# config-bank2.net
KiCad netlist of a schematic drawn in Altium Designer
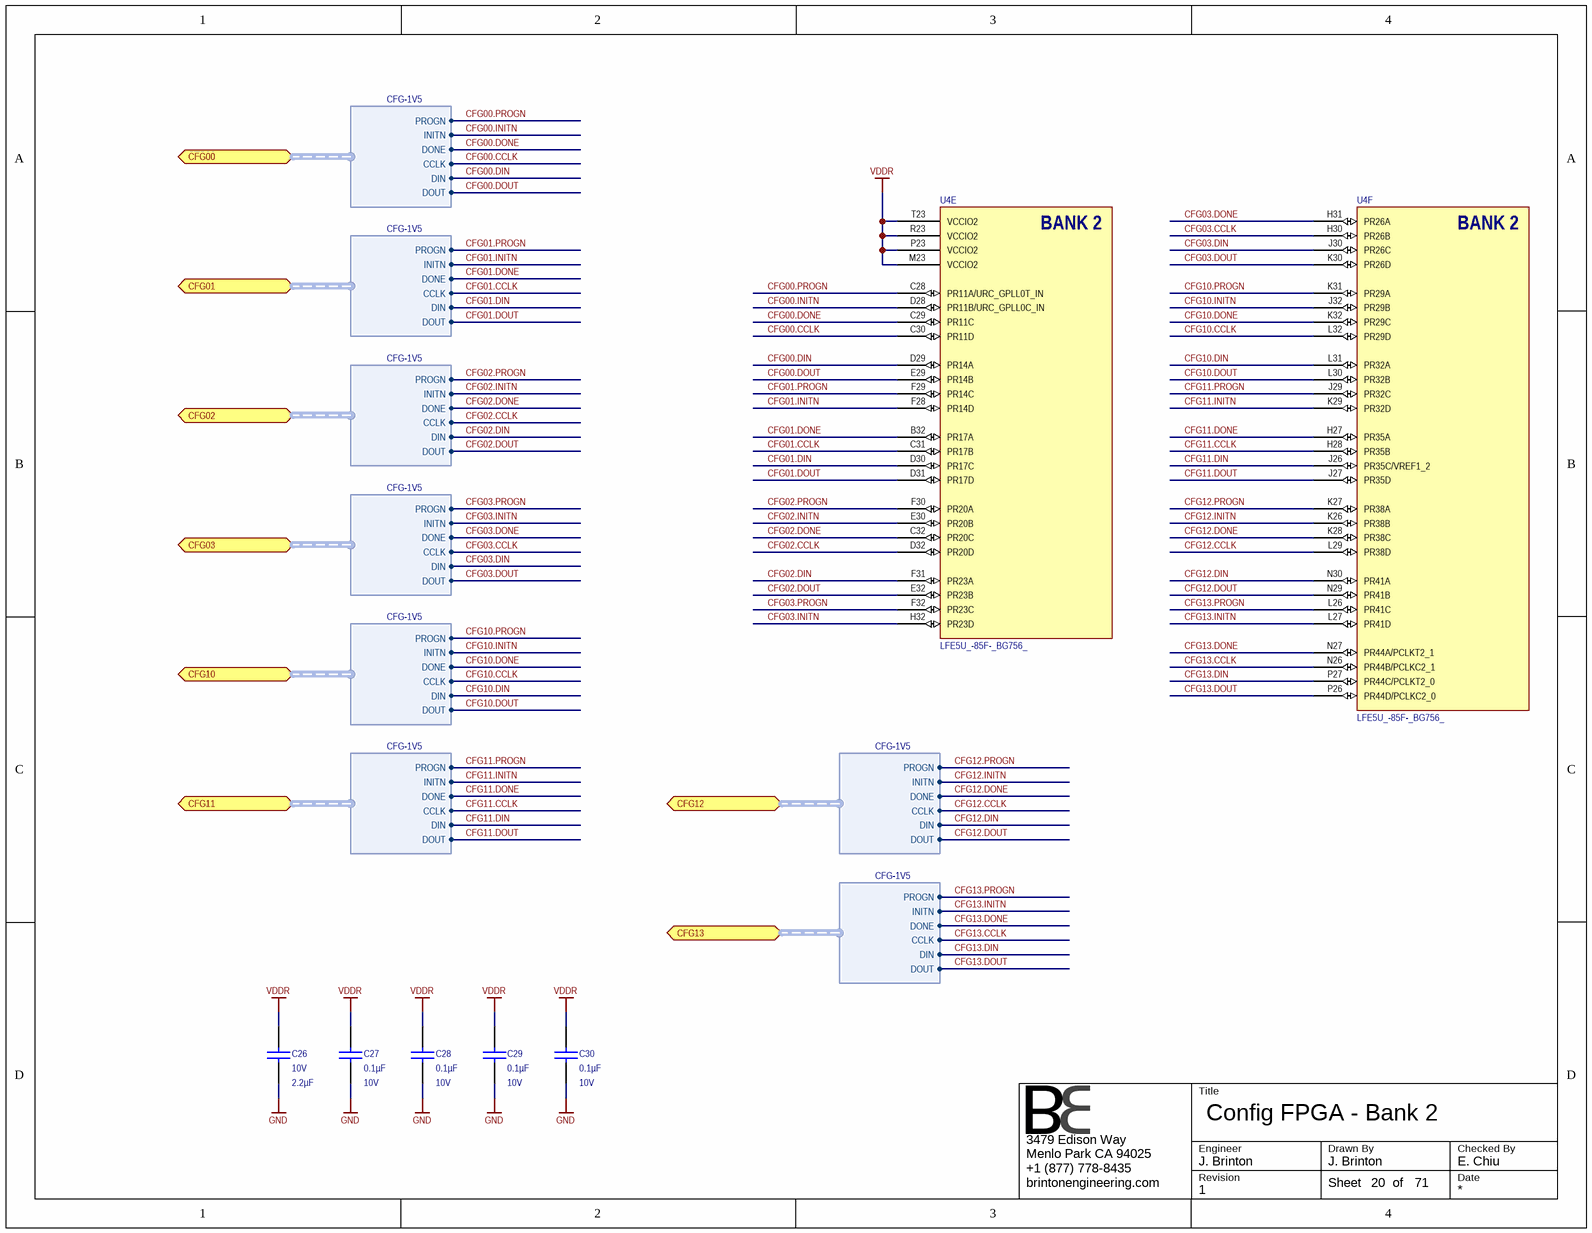
[diagram p0: config-bank2.SchDoc]

(export (version "E")
  (design (tool "Eeschema 10.0.6"))
  (components
    (comp (ref "C26")
      (value "GRM188R71A225KE15D")
      (footprint "CAPC1608X90N")
      (description "CAP CER 2.2UF 10V 10% X7R 0603")
      (fields
        (field (name "MANUFACTURER") "Murata Electronics North America")
        (field (name "TOLERANCE") "±10%")
        (field (name "VOLTAGE - RATED") "10V")
        (field (name "CAPACITANCE") "2.2µF")
      )
      (libsource (lib "murata") (part "GRM188R71A225KE15D"))
    )
    (comp (ref "C27")
      (value "GRM155R71A104KA01J")
      (footprint "CAPC1005X56N")
      (description "CAP CER 0.1UF 10V 10% X7R 0402")
      (fields
        (field (name "MANUFACTURER") "Murata Electronics North America")
        (field (name "TOLERANCE") "±10%")
        (field (name "CAPACITANCE") "0.1µF")
        (field (name "VOLTAGE - RATED") "10V")
      )
      (libsource (lib "murata") (part "GRM155R71A104KA01J"))
    )
    (comp (ref "C28")
      (value "GRM155R71A104KA01J")
      (footprint "CAPC1005X56N")
      (description "CAP CER 0.1UF 10V 10% X7R 0402")
      (fields
        (field (name "MANUFACTURER") "Murata Electronics North America")
        (field (name "TOLERANCE") "±10%")
        (field (name "CAPACITANCE") "0.1µF")
        (field (name "VOLTAGE - RATED") "10V")
      )
      (libsource (lib "murata") (part "GRM155R71A104KA01J"))
    )
    (comp (ref "C29")
      (value "GRM155R71A104KA01J")
      (footprint "CAPC1005X56N")
      (description "CAP CER 0.1UF 10V 10% X7R 0402")
      (fields
        (field (name "MANUFACTURER") "Murata Electronics North America")
        (field (name "TOLERANCE") "±10%")
        (field (name "CAPACITANCE") "0.1µF")
        (field (name "VOLTAGE - RATED") "10V")
      )
      (libsource (lib "murata") (part "GRM155R71A104KA01J"))
    )
    (comp (ref "C30")
      (value "GRM155R71A104KA01J")
      (footprint "CAPC1005X56N")
      (description "CAP CER 0.1UF 10V 10% X7R 0402")
      (fields
        (field (name "MANUFACTURER") "Murata Electronics North America")
        (field (name "TOLERANCE") "±10%")
        (field (name "CAPACITANCE") "0.1µF")
        (field (name "VOLTAGE - RATED") "10V")
      )
      (libsource (lib "murata") (part "GRM155R71A104KA01J"))
    )
    (comp (ref "U4")
      (value "LFE5U_-85F-_BG756_")
      (footprint "lattice:caBGA756")
      (description "ECP5 FPGA, 85k LUT, 756-caBGA")
      (fields (field (name "MANUFACTURER") "Lattice Semiconductor"))
      (libsource (lib "lattice") (part "LFE5U_-85F-_BG756_"))
    )
  )
  (nets
    (net (code "2") (name "/CFG00.CCLK") (class "Default")
      (node (ref "U4") (pin "C30") (pinfunction "PR11D_C30") (pintype "bidirectional"))
    )
    (net (code "3") (name "/CFG00.DIN") (class "Default")
      (node (ref "U4") (pin "D29") (pinfunction "PR14A_D29") (pintype "bidirectional"))
    )
    (net (code "4") (name "/CFG00.DONE") (class "Default")
      (node (ref "U4") (pin "C29") (pinfunction "PR11C_C29") (pintype "bidirectional"))
    )
    (net (code "5") (name "/CFG00.DOUT") (class "Default")
      (node (ref "U4") (pin "E29") (pinfunction "PR14B_E29") (pintype "bidirectional"))
    )
    (net (code "6") (name "/CFG00.INITN") (class "Default")
      (node (ref "U4") (pin "D28") (pinfunction "PR11B/URC_GPLL0C_IN_D28") (pintype "bidirectional"))
    )
    (net (code "7") (name "/CFG00.PROGN") (class "Default")
      (node (ref "U4") (pin "C28") (pinfunction "PR11A/URC_GPLL0T_IN_C28") (pintype "bidirectional"))
    )
    (net (code "8") (name "/CFG01.CCLK") (class "Default")
      (node (ref "U4") (pin "C31") (pinfunction "PR17B_C31") (pintype "bidirectional"))
    )
    (net (code "9") (name "/CFG01.DIN") (class "Default")
      (node (ref "U4") (pin "D30") (pinfunction "PR17C_D30") (pintype "bidirectional"))
    )
    (net (code "10") (name "/CFG01.DONE") (class "Default")
      (node (ref "U4") (pin "B32") (pinfunction "PR17A_B32") (pintype "bidirectional"))
    )
    (net (code "11") (name "/CFG01.DOUT") (class "Default")
      (node (ref "U4") (pin "D31") (pinfunction "PR17D_D31") (pintype "bidirectional"))
    )
    (net (code "12") (name "/CFG01.INITN") (class "Default")
      (node (ref "U4") (pin "F28") (pinfunction "PR14D_F28") (pintype "bidirectional"))
    )
    (net (code "13") (name "/CFG01.PROGN") (class "Default")
      (node (ref "U4") (pin "F29") (pinfunction "PR14C_F29") (pintype "bidirectional"))
    )
    (net (code "14") (name "/CFG02.CCLK") (class "Default")
      (node (ref "U4") (pin "D32") (pinfunction "PR20D_D32") (pintype "bidirectional"))
    )
    (net (code "15") (name "/CFG02.DIN") (class "Default")
      (node (ref "U4") (pin "F31") (pinfunction "PR23A_F31") (pintype "bidirectional"))
    )
    (net (code "16") (name "/CFG02.DONE") (class "Default")
      (node (ref "U4") (pin "C32") (pinfunction "PR20C_C32") (pintype "bidirectional"))
    )
    (net (code "17") (name "/CFG02.DOUT") (class "Default")
      (node (ref "U4") (pin "E32") (pinfunction "PR23B_E32") (pintype "bidirectional"))
    )
    (net (code "18") (name "/CFG02.INITN") (class "Default")
      (node (ref "U4") (pin "E30") (pinfunction "PR20B_E30") (pintype "bidirectional"))
    )
    (net (code "19") (name "/CFG02.PROGN") (class "Default")
      (node (ref "U4") (pin "F30") (pinfunction "PR20A_F30") (pintype "bidirectional"))
    )
    (net (code "20") (name "/CFG03.CCLK") (class "Default")
      (node (ref "U4") (pin "H30") (pinfunction "PR26B_H30") (pintype "bidirectional"))
    )
    (net (code "21") (name "/CFG03.DIN") (class "Default")
      (node (ref "U4") (pin "J30") (pinfunction "PR26C_J30") (pintype "bidirectional"))
    )
    (net (code "22") (name "/CFG03.DONE") (class "Default")
      (node (ref "U4") (pin "H31") (pinfunction "PR26A_H31") (pintype "bidirectional"))
    )
    (net (code "23") (name "/CFG03.DOUT") (class "Default")
      (node (ref "U4") (pin "K30") (pinfunction "PR26D_K30") (pintype "bidirectional"))
    )
    (net (code "24") (name "/CFG03.INITN") (class "Default")
      (node (ref "U4") (pin "H32") (pinfunction "PR23D_H32") (pintype "bidirectional"))
    )
    (net (code "25") (name "/CFG03.PROGN") (class "Default")
      (node (ref "U4") (pin "F32") (pinfunction "PR23C_F32") (pintype "bidirectional"))
    )
    (net (code "26") (name "/CFG10.CCLK") (class "Default")
      (node (ref "U4") (pin "L32") (pinfunction "PR29D_L32") (pintype "bidirectional"))
    )
    (net (code "27") (name "/CFG10.DIN") (class "Default")
      (node (ref "U4") (pin "L31") (pinfunction "PR32A_L31") (pintype "bidirectional"))
    )
    (net (code "28") (name "/CFG10.DONE") (class "Default")
      (node (ref "U4") (pin "K32") (pinfunction "PR29C_K32") (pintype "bidirectional"))
    )
    (net (code "29") (name "/CFG10.DOUT") (class "Default")
      (node (ref "U4") (pin "L30") (pinfunction "PR32B_L30") (pintype "bidirectional"))
    )
    (net (code "30") (name "/CFG10.INITN") (class "Default")
      (node (ref "U4") (pin "J32") (pinfunction "PR29B_J32") (pintype "bidirectional"))
    )
    (net (code "31") (name "/CFG10.PROGN") (class "Default")
      (node (ref "U4") (pin "K31") (pinfunction "PR29A_K31") (pintype "bidirectional"))
    )
    (net (code "32") (name "/CFG11.CCLK") (class "Default")
      (node (ref "U4") (pin "H28") (pinfunction "PR35B_H28") (pintype "bidirectional"))
    )
    (net (code "33") (name "/CFG11.DIN") (class "Default")
      (node (ref "U4") (pin "J26") (pinfunction "PR35C/VREF1_2_J26") (pintype "bidirectional"))
    )
    (net (code "34") (name "/CFG11.DONE") (class "Default")
      (node (ref "U4") (pin "H27") (pinfunction "PR35A_H27") (pintype "bidirectional"))
    )
    (net (code "35") (name "/CFG11.DOUT") (class "Default")
      (node (ref "U4") (pin "J27") (pinfunction "PR35D_J27") (pintype "bidirectional"))
    )
    (net (code "36") (name "/CFG11.INITN") (class "Default")
      (node (ref "U4") (pin "K29") (pinfunction "PR32D_K29") (pintype "bidirectional"))
    )
    (net (code "37") (name "/CFG11.PROGN") (class "Default")
      (node (ref "U4") (pin "J29") (pinfunction "PR32C_J29") (pintype "bidirectional"))
    )
    (net (code "38") (name "/CFG12.CCLK") (class "Default")
      (node (ref "U4") (pin "L29") (pinfunction "PR38D_L29") (pintype "bidirectional"))
    )
    (net (code "39") (name "/CFG12.DIN") (class "Default")
      (node (ref "U4") (pin "N30") (pinfunction "PR41A_N30") (pintype "bidirectional"))
    )
    (net (code "40") (name "/CFG12.DONE") (class "Default")
      (node (ref "U4") (pin "K28") (pinfunction "PR38C_K28") (pintype "bidirectional"))
    )
    (net (code "41") (name "/CFG12.DOUT") (class "Default")
      (node (ref "U4") (pin "N29") (pinfunction "PR41B_N29") (pintype "bidirectional"))
    )
    (net (code "42") (name "/CFG12.INITN") (class "Default")
      (node (ref "U4") (pin "K26") (pinfunction "PR38B_K26") (pintype "bidirectional"))
    )
    (net (code "43") (name "/CFG12.PROGN") (class "Default")
      (node (ref "U4") (pin "K27") (pinfunction "PR38A_K27") (pintype "bidirectional"))
    )
    (net (code "44") (name "/CFG13.CCLK") (class "Default")
      (node (ref "U4") (pin "N26") (pinfunction "PR44B/PCLKC2_1_N26") (pintype "bidirectional"))
    )
    (net (code "45") (name "/CFG13.DIN") (class "Default")
      (node (ref "U4") (pin "P27") (pinfunction "PR44C/PCLKT2_0_P27") (pintype "bidirectional"))
    )
    (net (code "46") (name "/CFG13.DONE") (class "Default")
      (node (ref "U4") (pin "N27") (pinfunction "PR44A/PCLKT2_1_N27") (pintype "bidirectional"))
    )
    (net (code "47") (name "/CFG13.DOUT") (class "Default")
      (node (ref "U4") (pin "P26") (pinfunction "PR44D/PCLKC2_0_P26") (pintype "bidirectional"))
    )
    (net (code "48") (name "/CFG13.INITN") (class "Default")
      (node (ref "U4") (pin "L27") (pinfunction "PR41D_L27") (pintype "bidirectional"))
    )
    (net (code "49") (name "/CFG13.PROGN") (class "Default")
      (node (ref "U4") (pin "L26") (pinfunction "PR41C_L26") (pintype "bidirectional"))
    )
    (net (code "51") (name "GND") (class "Default")
      (node (ref "C26") (pin "1") (pinfunction "1_1") (pintype "passive"))
      (node (ref "C27") (pin "1") (pinfunction "1_1") (pintype "passive"))
      (node (ref "C28") (pin "1") (pinfunction "1_1") (pintype "passive"))
      (node (ref "C29") (pin "1") (pinfunction "1_1") (pintype "passive"))
      (node (ref "C30") (pin "1") (pinfunction "1_1") (pintype "passive"))
    )
    (net (code "52") (name "VDDR") (class "Default")
      (node (ref "C26") (pin "2") (pinfunction "2_2") (pintype "passive"))
      (node (ref "C27") (pin "2") (pinfunction "2_2") (pintype "passive"))
      (node (ref "C28") (pin "2") (pinfunction "2_2") (pintype "passive"))
      (node (ref "C29") (pin "2") (pinfunction "2_2") (pintype "passive"))
      (node (ref "C30") (pin "2") (pinfunction "2_2") (pintype "passive"))
      (node (ref "U4") (pin "M23") (pinfunction "VCCIO2_M23") (pintype "power_in"))
      (node (ref "U4") (pin "P23") (pinfunction "VCCIO2_P23") (pintype "power_in"))
      (node (ref "U4") (pin "R23") (pinfunction "VCCIO2_R23") (pintype "power_in"))
      (node (ref "U4") (pin "T23") (pinfunction "VCCIO2_T23") (pintype "power_in"))
    )
  )
)
